# OPAMP_TESTER_2.net
KiCad netlist of a schematic drawn in Altium Designer
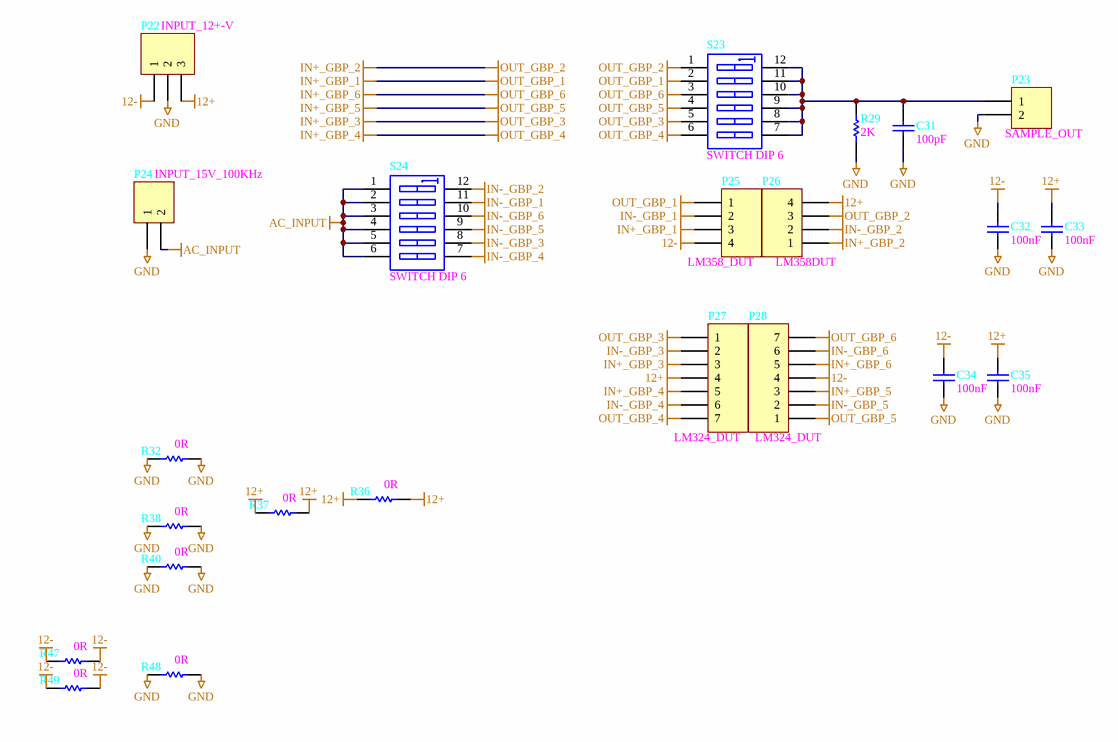
[diagram p0: OPAMP_TESTER_2.SchDoc]

(export (version "E")
  (design (tool "Eeschema 10.0.6"))
  (components
    (comp (ref "C31")
      (value "100pF")
      (footprint "SMD 0805")
      (description "Capacitor")
      (fields (field (name "PUBLISHER") "Altium Limited"))
      (libsource (lib "Parlarlib_30") (part "CAP"))
    )
    (comp (ref "C32")
      (value "100nF")
      (footprint "SMD 0805")
      (description "Capacitor")
      (fields (field (name "PUBLISHER") "Altium Limited"))
      (libsource (lib "Parlarlib_30") (part "CAP"))
    )
    (comp (ref "C33")
      (value "100nF")
      (footprint "SMD 0805")
      (description "Capacitor")
      (fields (field (name "PUBLISHER") "Altium Limited"))
      (libsource (lib "Parlarlib_30") (part "CAP"))
    )
    (comp (ref "C34")
      (value "100nF")
      (footprint "SMD 1206")
      (description "Capacitor")
      (fields (field (name "PUBLISHER") "Altium Limited"))
      (libsource (lib "Parlarlib_30") (part "CAP"))
    )
    (comp (ref "C35")
      (value "100nF")
      (footprint "SMD 1206")
      (description "Capacitor")
      (fields (field (name "PUBLISHER") "Altium Limited"))
      (libsource (lib "Parlarlib_30") (part "CAP"))
    )
    (comp (ref "P22")
      (value "INPUT_12+-V")
      (footprint "CON XH 3")
      (description "Header, 3-Pin")
      (fields (field (name "PUBLISHER") "Altium Limited"))
      (libsource (lib "Parlarlib_30") (part "CONNECTOR 3"))
    )
    (comp (ref "P23")
      (value "SAMPLE_OUT")
      (footprint "CON XH 2")
      (description "Header, 2-Pin")
      (fields (field (name "PUBLISHER") "Altium Limited"))
      (libsource (lib "") (part "CONNECTOR 2_1"))
    )
    (comp (ref "P24")
      (value "INPUT_15V_100KHz")
      (footprint "CON XH 2")
      (description "Header, 2-Pin")
      (fields (field (name "PUBLISHER") "Altium Limited"))
      (libsource (lib "Parlarlib_30") (part "CONNECTOR 2"))
    )
    (comp (ref "P25")
      (value "LM358_DUT")
      (footprint "CON HDR 2.54FM 4")
      (description "Header, 4-Pin")
      (fields (field (name "PUBLISHER") "Altium Limited"))
      (libsource (lib "") (part "CONNECTOR 4_1"))
    )
    (comp (ref "P26")
      (value "LM358DUT")
      (footprint "CON HDR 2.54FM 4")
      (description "Header, 4-Pin")
      (fields (field (name "PUBLISHER") "Altium Limited"))
      (libsource (lib "Parlarlib_30") (part "CONNECTOR 4"))
    )
    (comp (ref "P27")
      (value "LM324_DUT")
      (footprint "CON HDR 2.54FM 7")
      (description "Header, 7-Pin")
      (fields (field (name "PUBLISHER") "Altium Limited"))
      (libsource (lib "Parlarlib_30") (part "CONNECTOR 7"))
    )
    (comp (ref "P28")
      (value "LM324_DUT")
      (footprint "CON HDR 2.54FM 7")
      (description "Header, 7-Pin")
      (fields (field (name "PUBLISHER") "Altium Limited"))
      (libsource (lib "") (part "CONNECTOR 7_1"))
    )
    (comp (ref "R29")
      (value "2K")
      (footprint "SMD 0805")
      (description "Resistor")
      (libsource (lib "Parlarlib_30") (part "RES"))
    )
    (comp (ref "R32")
      (value "0R")
      (footprint "SMD 1206")
      (description "Resistor")
      (libsource (lib "Parlarlib_30") (part "RES"))
    )
    (comp (ref "R36")
      (value "0R")
      (footprint "SMD 1206")
      (description "Resistor")
      (libsource (lib "Parlarlib_30") (part "RES"))
    )
    (comp (ref "R37")
      (value "0R")
      (footprint "SMD 1206")
      (description "Resistor")
      (libsource (lib "Parlarlib_30") (part "RES"))
    )
    (comp (ref "R38")
      (value "0R")
      (footprint "SMD 1206")
      (description "Resistor")
      (libsource (lib "Parlarlib_30") (part "RES"))
    )
    (comp (ref "R40")
      (value "0R")
      (footprint "SMD 1206")
      (description "Resistor")
      (libsource (lib "Parlarlib_30") (part "RES"))
    )
    (comp (ref "R47")
      (value "0R")
      (footprint "SMD 1206")
      (description "Resistor")
      (libsource (lib "Parlarlib_30") (part "RES"))
    )
    (comp (ref "R48")
      (value "0R")
      (footprint "SMD 1206")
      (description "Resistor")
      (libsource (lib "Parlarlib_30") (part "RES"))
    )
    (comp (ref "R49")
      (value "0R")
      (footprint "SMD 1206")
      (description "Resistor")
      (libsource (lib "Parlarlib_30") (part "RES"))
    )
    (comp (ref "S23")
      (value "SWITCH DIP 6")
      (footprint "SWITCH DIP 6")
      (description "DIP Switch, 6 Position, SPST")
      (fields (field (name "PUBLISHER") "Altium Limited"))
      (libsource (lib "Parlarlib_30") (part "SWITCH DIP 6"))
    )
    (comp (ref "S24")
      (value "SWITCH DIP 6")
      (footprint "SWITCH DIP 6")
      (description "DIP Switch, 6 Position, SPST")
      (fields (field (name "PUBLISHER") "Altium Limited"))
      (libsource (lib "Parlarlib_30") (part "SWITCH DIP 6"))
    )
  )
  (nets
    (net (code "1") (name "12+") (class "Default")
      (node (ref "C33") (pin "2") (pinfunction "2_2") (pintype "passive"))
      (node (ref "C35") (pin "2") (pinfunction "2_2") (pintype "passive"))
      (node (ref "P22") (pin "3") (pinfunction "3_3") (pintype "passive"))
      (node (ref "P26") (pin "4") (pinfunction "4_4") (pintype "passive"))
      (node (ref "P27") (pin "4") (pinfunction "4_4") (pintype "passive"))
      (node (ref "R36") (pin "1") (pinfunction "1_1") (pintype "passive"))
      (node (ref "R36") (pin "2") (pinfunction "2_2") (pintype "passive"))
      (node (ref "R37") (pin "1") (pinfunction "1_1") (pintype "passive"))
      (node (ref "R37") (pin "2") (pinfunction "2_2") (pintype "passive"))
    )
    (net (code "2") (name "12-") (class "Default")
      (node (ref "C32") (pin "2") (pinfunction "2_2") (pintype "passive"))
      (node (ref "C34") (pin "2") (pinfunction "2_2") (pintype "passive"))
      (node (ref "P22") (pin "1") (pinfunction "1_1") (pintype "passive"))
      (node (ref "P25") (pin "4") (pinfunction "4_4") (pintype "passive"))
      (node (ref "P28") (pin "4") (pinfunction "4_4") (pintype "passive"))
      (node (ref "R47") (pin "1") (pinfunction "1_1") (pintype "passive"))
      (node (ref "R47") (pin "2") (pinfunction "2_2") (pintype "passive"))
      (node (ref "R49") (pin "1") (pinfunction "1_1") (pintype "passive"))
      (node (ref "R49") (pin "2") (pinfunction "2_2") (pintype "passive"))
    )
    (net (code "3") (name "AC_INPUT") (class "Default")
      (node (ref "P24") (pin "2") (pinfunction "2_2") (pintype "passive"))
      (node (ref "S24") (pin "1") (pinfunction "A1_1") (pintype "passive"))
      (node (ref "S24") (pin "2") (pinfunction "A2_2") (pintype "passive"))
      (node (ref "S24") (pin "3") (pinfunction "A3_3") (pintype "passive"))
      (node (ref "S24") (pin "4") (pinfunction "A4_4") (pintype "passive"))
      (node (ref "S24") (pin "5") (pinfunction "A5_5") (pintype "passive"))
      (node (ref "S24") (pin "6") (pinfunction "A6_6") (pintype "passive"))
    )
    (net (code "4") (name "GND") (class "Default")
      (node (ref "C31") (pin "1") (pinfunction "1_1") (pintype "passive"))
      (node (ref "C32") (pin "1") (pinfunction "1_1") (pintype "passive"))
      (node (ref "C33") (pin "1") (pinfunction "1_1") (pintype "passive"))
      (node (ref "C34") (pin "1") (pinfunction "1_1") (pintype "passive"))
      (node (ref "C35") (pin "1") (pinfunction "1_1") (pintype "passive"))
      (node (ref "P22") (pin "2") (pinfunction "2_2") (pintype "passive"))
      (node (ref "P23") (pin "2") (pinfunction "2_2") (pintype "passive"))
      (node (ref "P24") (pin "1") (pinfunction "1_1") (pintype "passive"))
      (node (ref "R29") (pin "2") (pinfunction "2_2") (pintype "passive"))
      (node (ref "R32") (pin "1") (pinfunction "1_1") (pintype "passive"))
      (node (ref "R32") (pin "2") (pinfunction "2_2") (pintype "passive"))
      (node (ref "R38") (pin "1") (pinfunction "1_1") (pintype "passive"))
      (node (ref "R38") (pin "2") (pinfunction "2_2") (pintype "passive"))
      (node (ref "R40") (pin "1") (pinfunction "1_1") (pintype "passive"))
      (node (ref "R40") (pin "2") (pinfunction "2_2") (pintype "passive"))
      (node (ref "R48") (pin "1") (pinfunction "1_1") (pintype "passive"))
      (node (ref "R48") (pin "2") (pinfunction "2_2") (pintype "passive"))
    )
    (net (code "5") (name "IN+_GBP_1") (class "Default")
      (node (ref "P25") (pin "1") (pinfunction "1_1") (pintype "passive"))
      (node (ref "P25") (pin "3") (pinfunction "3_3") (pintype "passive"))
      (node (ref "S23") (pin "2") (pinfunction "A2_2") (pintype "passive"))
    )
    (net (code "6") (name "IN+_GBP_2") (class "Default")
      (node (ref "P26") (pin "1") (pinfunction "1_1") (pintype "passive"))
      (node (ref "P26") (pin "3") (pinfunction "3_3") (pintype "passive"))
      (node (ref "S23") (pin "1") (pinfunction "A1_1") (pintype "passive"))
    )
    (net (code "7") (name "IN+_GBP_3") (class "Default")
      (node (ref "P27") (pin "1") (pinfunction "1_1") (pintype "passive"))
      (node (ref "P27") (pin "3") (pinfunction "3_3") (pintype "passive"))
      (node (ref "S23") (pin "5") (pinfunction "A5_5") (pintype "passive"))
    )
    (net (code "8") (name "IN+_GBP_4") (class "Default")
      (node (ref "P27") (pin "5") (pinfunction "5_5") (pintype "passive"))
      (node (ref "P27") (pin "7") (pinfunction "7_7") (pintype "passive"))
      (node (ref "S23") (pin "6") (pinfunction "A6_6") (pintype "passive"))
    )
    (net (code "9") (name "IN+_GBP_5") (class "Default")
      (node (ref "P28") (pin "1") (pinfunction "1_1") (pintype "passive"))
      (node (ref "P28") (pin "3") (pinfunction "3_3") (pintype "passive"))
      (node (ref "S23") (pin "4") (pinfunction "A4_4") (pintype "passive"))
    )
    (net (code "10") (name "IN+_GBP_6") (class "Default")
      (node (ref "P28") (pin "5") (pinfunction "5_5") (pintype "passive"))
      (node (ref "P28") (pin "7") (pinfunction "7_7") (pintype "passive"))
      (node (ref "S23") (pin "3") (pinfunction "A3_3") (pintype "passive"))
    )
    (net (code "11") (name "IN-_GBP_1") (class "Default")
      (node (ref "P25") (pin "2") (pinfunction "2_2") (pintype "passive"))
      (node (ref "S24") (pin "11") (pinfunction "B2_11") (pintype "passive"))
    )
    (net (code "12") (name "IN-_GBP_2") (class "Default")
      (node (ref "P26") (pin "2") (pinfunction "2_2") (pintype "passive"))
      (node (ref "S24") (pin "12") (pinfunction "B1_12") (pintype "passive"))
    )
    (net (code "13") (name "IN-_GBP_3") (class "Default")
      (node (ref "P27") (pin "2") (pinfunction "2_2") (pintype "passive"))
      (node (ref "S24") (pin "8") (pinfunction "B5_8") (pintype "passive"))
    )
    (net (code "14") (name "IN-_GBP_4") (class "Default")
      (node (ref "P27") (pin "6") (pinfunction "6_6") (pintype "passive"))
      (node (ref "S24") (pin "7") (pinfunction "B6_7") (pintype "passive"))
    )
    (net (code "15") (name "IN-_GBP_5") (class "Default")
      (node (ref "P28") (pin "2") (pinfunction "2_2") (pintype "passive"))
      (node (ref "S24") (pin "9") (pinfunction "B4_9") (pintype "passive"))
    )
    (net (code "16") (name "IN-_GBP_6") (class "Default")
      (node (ref "P28") (pin "6") (pinfunction "6_6") (pintype "passive"))
      (node (ref "S24") (pin "10") (pinfunction "B3_10") (pintype "passive"))
    )
    (net (code "17") (name "Net-(S23-B1)") (class "Default")
      (node (ref "C31") (pin "2") (pinfunction "2_2") (pintype "passive"))
      (node (ref "P23") (pin "1") (pinfunction "1_1") (pintype "passive"))
      (node (ref "R29") (pin "1") (pinfunction "1_1") (pintype "passive"))
      (node (ref "S23") (pin "10") (pinfunction "B3_10") (pintype "passive"))
      (node (ref "S23") (pin "11") (pinfunction "B2_11") (pintype "passive"))
      (node (ref "S23") (pin "12") (pinfunction "B1_12") (pintype "passive"))
      (node (ref "S23") (pin "7") (pinfunction "B6_7") (pintype "passive"))
      (node (ref "S23") (pin "8") (pinfunction "B5_8") (pintype "passive"))
      (node (ref "S23") (pin "9") (pinfunction "B4_9") (pintype "passive"))
    )
  )
)
